# pain.net
KiCad netlist of a schematic drawn in EAGLE
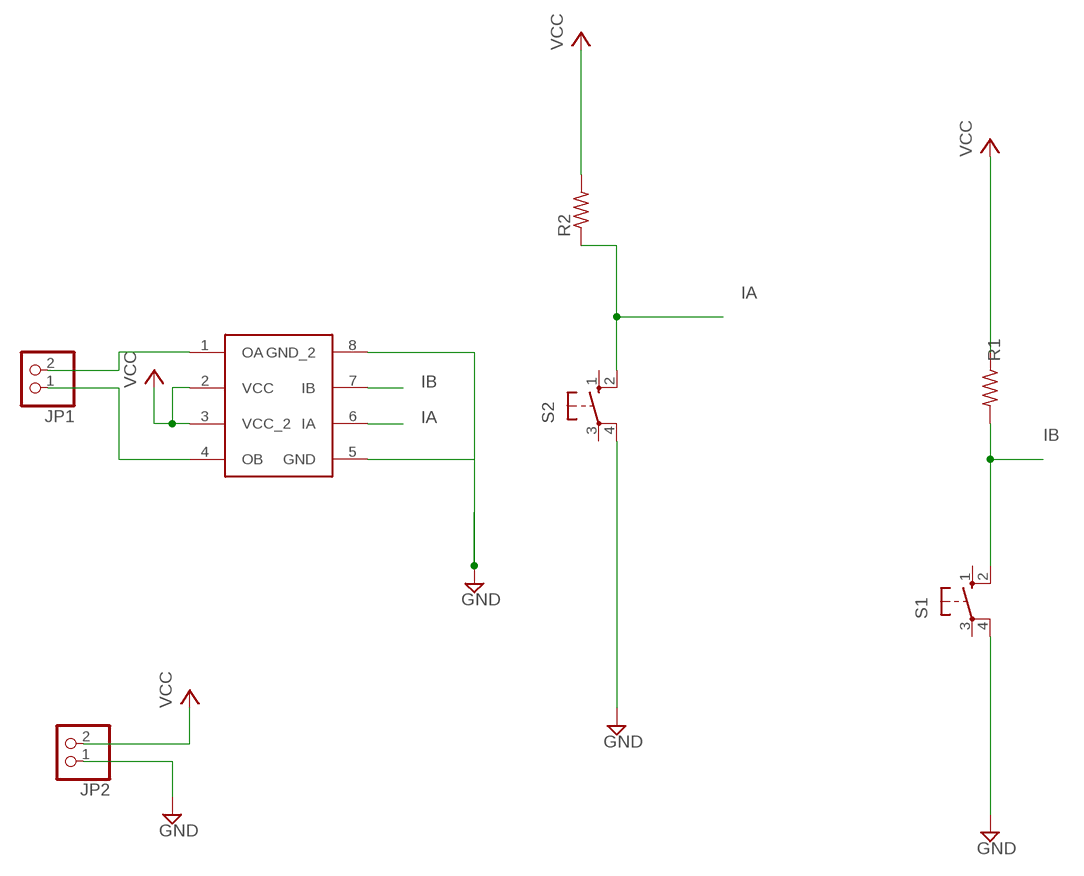
[diagram p0: schematic, sheet 1]

(export (version "E")
  (design (tool "Eeschema 10.0.6"))
  (components
    (comp (ref "JP1")
      (value "PINHD-1X2")
      (footprint "eagle-import:1X02")
      (libsource (lib "eagle-import") (part "PINHD-1X2"))
    )
    (comp (ref "JP2")
      (value "PINHD-1X2")
      (footprint "eagle-import:1X02")
      (libsource (lib "eagle-import") (part "PINHD-1X2"))
    )
    (comp (ref "R1")
      (value "R-US_R0603")
      (footprint "eagle-import:R0603")
      (libsource (lib "eagle-import") (part "R-US_R0603"))
    )
    (comp (ref "R2")
      (value "R-US_R0603")
      (footprint "eagle-import:R0603")
      (libsource (lib "eagle-import") (part "R-US_R0603"))
    )
    (comp (ref "S1")
      (value "40-XX")
      (footprint "eagle-import:B3F-40XX")
      (fields (field (name "MF") "OMRON COMPONENTS USA") (field (name "MPN") "B3F-4000"))
      (libsource (lib "eagle-import") (part "40-XX"))
    )
    (comp (ref "S2")
      (value "40-XX")
      (footprint "eagle-import:B3F-40XX")
      (fields (field (name "MF") "OMRON COMPONENTS USA") (field (name "MPN") "B3F-4000"))
      (libsource (lib "eagle-import") (part "40-XX"))
    )
    (comp (ref "U$1")
      (value "L9110")
      (footprint "eagle-import:DIP8")
      (libsource (lib "eagle-import") (part "L9110"))
    )
  )
  (nets
    (net (code "1") (name "/IA") (class "Default")
      (node (ref "R2") (pin "1") (pinfunction "1_1") (pintype "passive"))
      (node (ref "S2") (pin "2") (pinfunction "S1_2") (pintype "passive"))
      (node (ref "U$1") (pin "6") (pinfunction "IA_6") (pintype "bidirectional"))
    )
    (net (code "2") (name "/IB") (class "Default")
      (node (ref "R1") (pin "2") (pinfunction "2_2") (pintype "passive"))
      (node (ref "S1") (pin "2") (pinfunction "S1_2") (pintype "passive"))
      (node (ref "U$1") (pin "7") (pinfunction "IB_7") (pintype "bidirectional"))
    )
    (net (code "3") (name "GND") (class "Default")
      (node (ref "JP2") (pin "1") (pinfunction "1_1") (pintype "passive"))
      (node (ref "S1") (pin "4") (pinfunction "P1_4") (pintype "passive"))
      (node (ref "S2") (pin "4") (pinfunction "P1_4") (pintype "passive"))
      (node (ref "U$1") (pin "5") (pinfunction "GND_5") (pintype "bidirectional"))
      (node (ref "U$1") (pin "8") (pinfunction "GND_2_8") (pintype "bidirectional"))
    )
    (net (code "4") (name "Net-(U$1-OA)") (class "Default")
      (node (ref "JP1") (pin "2") (pinfunction "2_2") (pintype "passive"))
      (node (ref "U$1") (pin "1") (pinfunction "OA_1") (pintype "bidirectional"))
    )
    (net (code "5") (name "Net-(U$1-OB)") (class "Default")
      (node (ref "JP1") (pin "1") (pinfunction "1_1") (pintype "passive"))
      (node (ref "U$1") (pin "4") (pinfunction "OB_4") (pintype "bidirectional"))
    )
    (net (code "6") (name "VCC") (class "Default")
      (node (ref "JP2") (pin "2") (pinfunction "2_2") (pintype "passive"))
      (node (ref "R1") (pin "1") (pinfunction "1_1") (pintype "passive"))
      (node (ref "R2") (pin "2") (pinfunction "2_2") (pintype "passive"))
      (node (ref "U$1") (pin "2") (pinfunction "VCC_2") (pintype "bidirectional"))
      (node (ref "U$1") (pin "3") (pinfunction "VCC_2_3") (pintype "bidirectional"))
    )
    (net (code "7") (name "unconnected-(S1-P-Pad3)") (class "Default")
      (node (ref "S1") (pin "3") (pinfunction "P_3") (pintype "passive"))
    )
    (net (code "8") (name "unconnected-(S1-S-Pad1)") (class "Default")
      (node (ref "S1") (pin "1") (pinfunction "S_1") (pintype "passive"))
    )
    (net (code "9") (name "unconnected-(S2-P-Pad3)") (class "Default")
      (node (ref "S2") (pin "3") (pinfunction "P_3") (pintype "passive"))
    )
    (net (code "10") (name "unconnected-(S2-S-Pad1)") (class "Default")
      (node (ref "S2") (pin "1") (pinfunction "S_1") (pintype "passive"))
    )
  )
)
